# keyboard.net
KiCad netlist of a schematic drawn in EAGLE
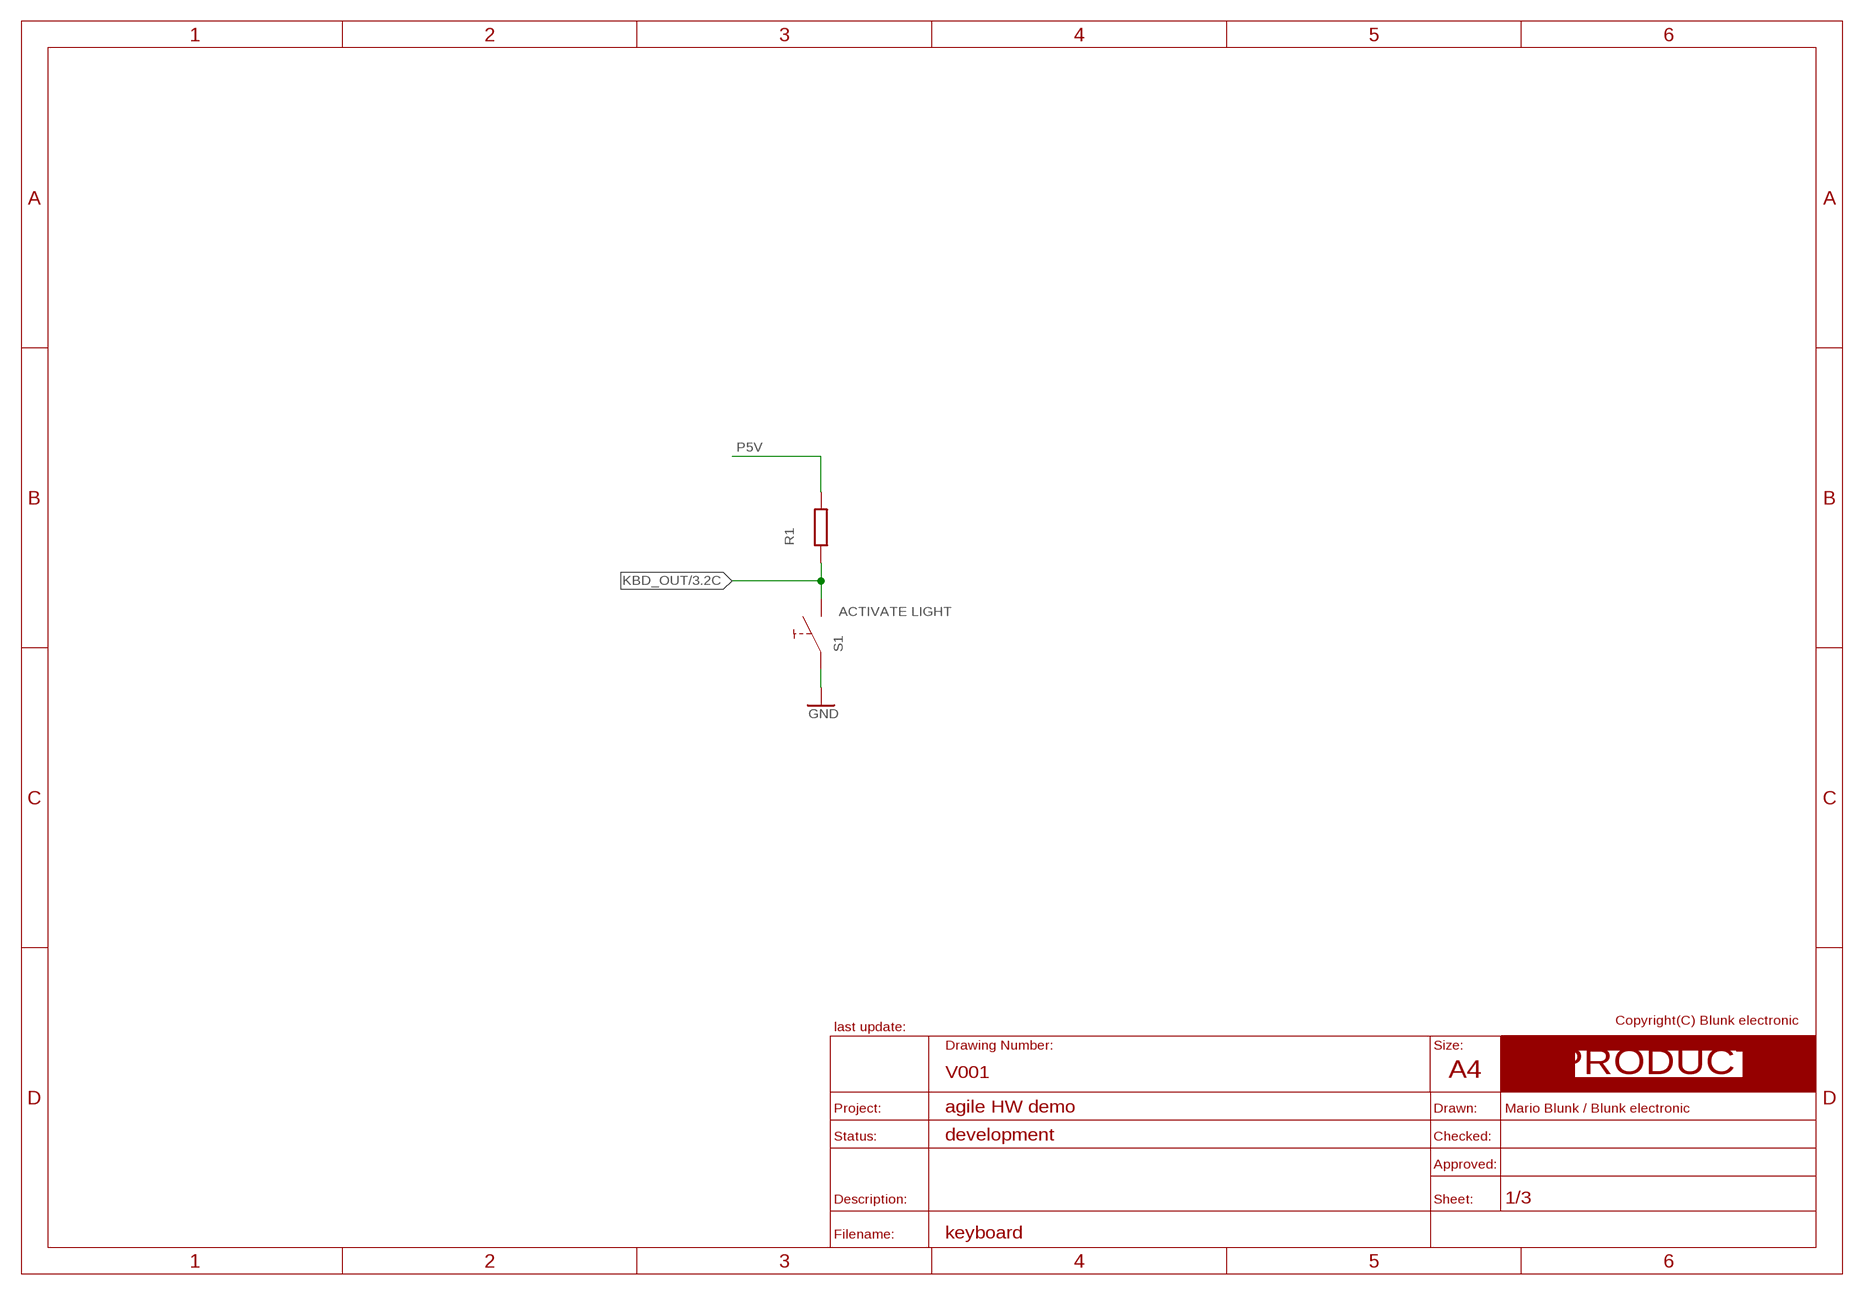
[diagram p0: schematic, sheet 1]
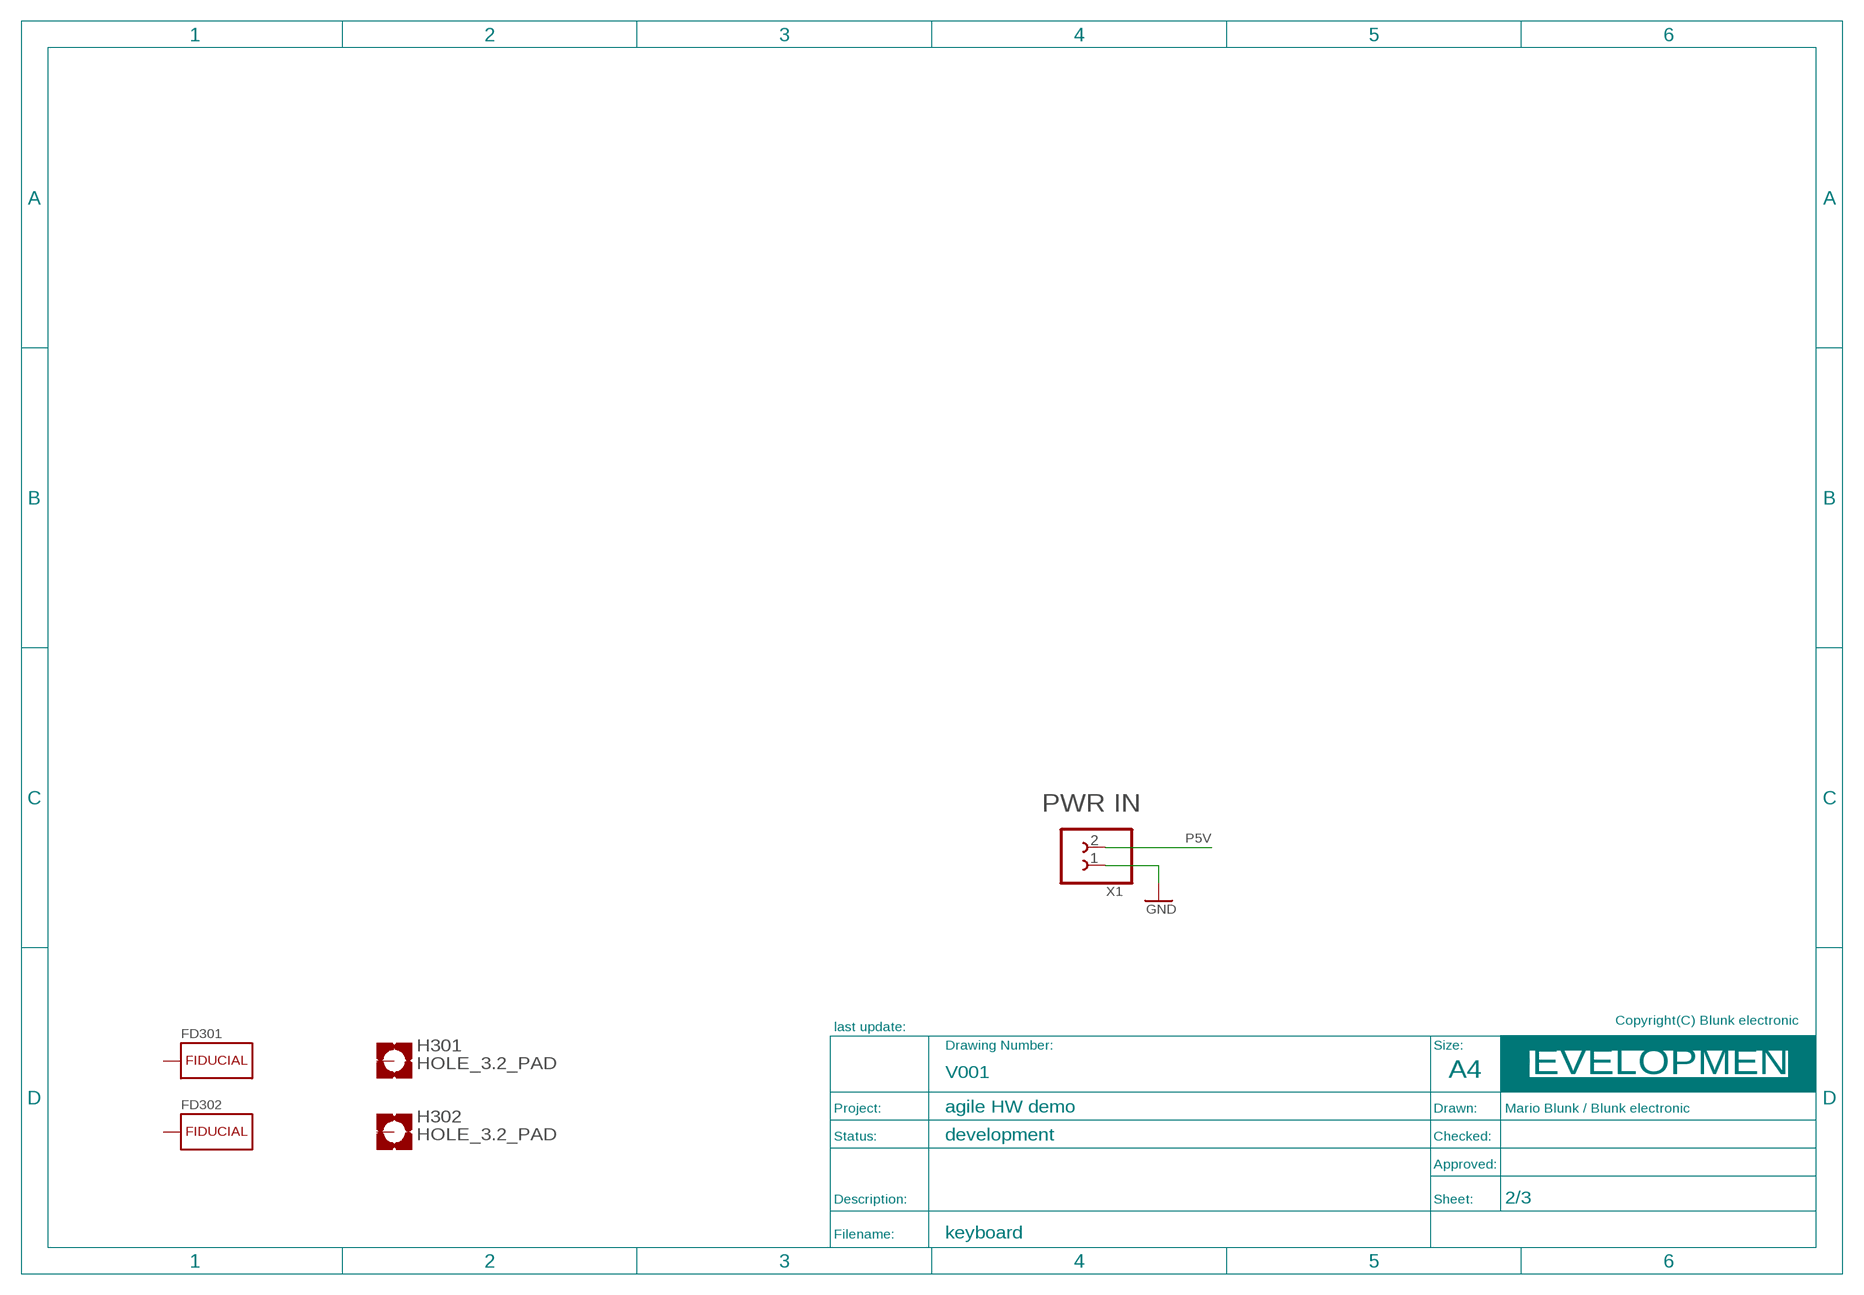
[diagram p1: schematic, sheet 2]
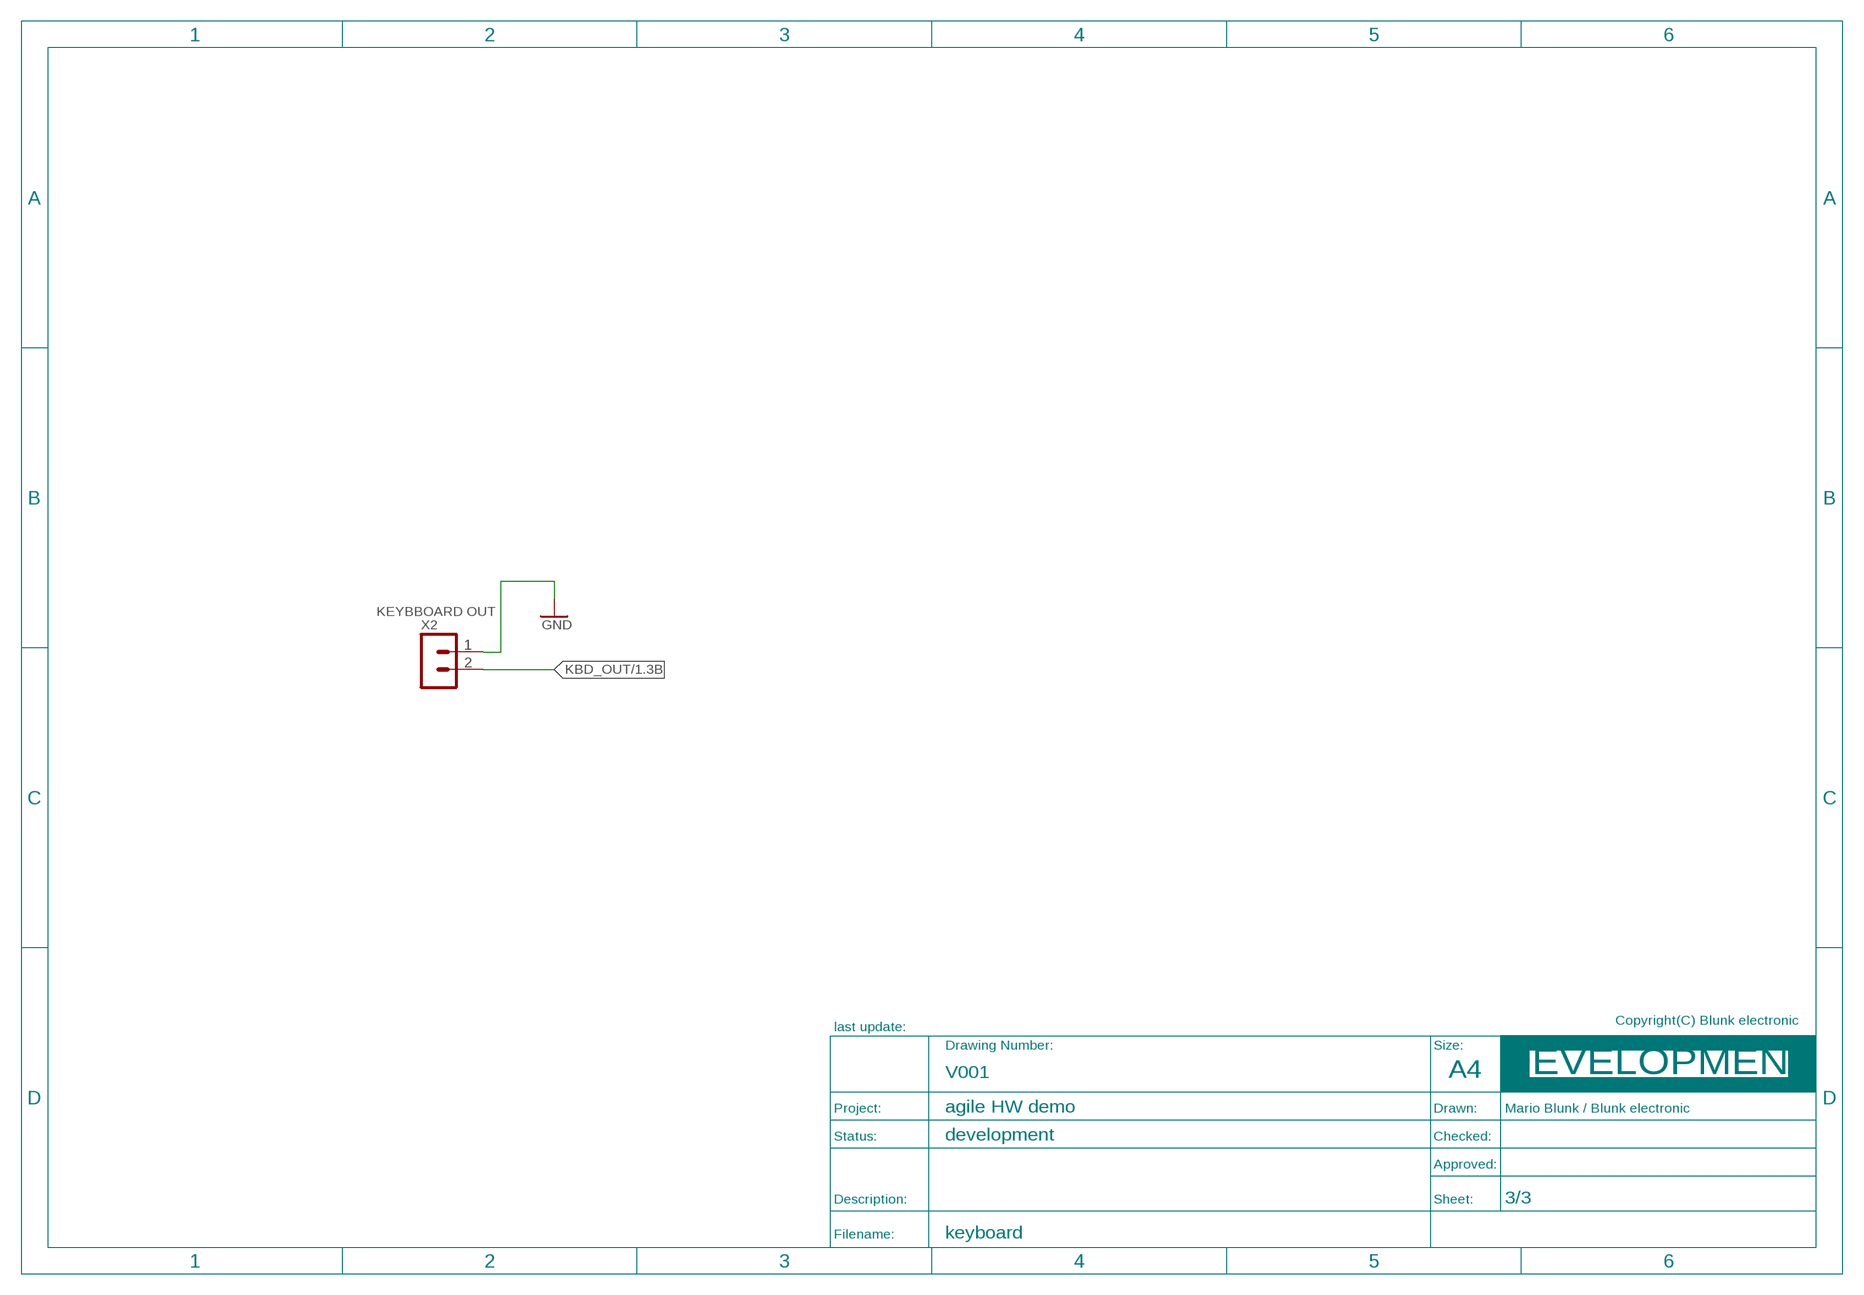
[diagram p2: schematic, sheet 3]

(export (version "E")
  (design (tool "Eeschema 10.0.6"))
  (components
    (comp (ref "FD301")
      (value "FIDUCIAL_CROSSHAIR")
      (footprint "eagle-import:CROSSHAIR")
      (libsource (lib "eagle-import") (part "FIDUCIAL_CROSSHAIR"))
    )
    (comp (ref "FD302")
      (value "FIDUCIAL_CROSSHAIR")
      (footprint "eagle-import:CROSSHAIR")
      (libsource (lib "eagle-import") (part "FIDUCIAL_CROSSHAIR"))
    )
    (comp (ref "H301")
      (value "HOLE_3.2_PAD")
      (footprint "eagle-import:3.2_PAD")
      (libsource (lib "eagle-import") (part "HOLE_3.2_PAD"))
    )
    (comp (ref "H302")
      (value "HOLE_3.2_PAD")
      (footprint "eagle-import:3.2_PAD")
      (libsource (lib "eagle-import") (part "HOLE_3.2_PAD"))
    )
    (comp (ref "X1")
      (value "CLAMP_1X2-T-2.5MM")
      (footprint "eagle-import:T_WIRE_CLAMP_1X2_PITCH_2MM5")
      (fields (field (name "FUNCTION") "PWR IN"))
      (libsource (lib "eagle-import") (part "CLAMP_1X2-T-2.5MM"))
    )
    (comp (ref "R1")
      (value "R_S_0805")
      (footprint "eagle-import:S_0805")
      (libsource (lib "eagle-import") (part "R_S_0805"))
    )
    (comp (ref "S1")
      (value "PUSH_BUTTON_S_6X6MM")
      (footprint "eagle-import:S_PUSH_BUTTON_6X6")
      (fields (field (name "FUNCTION") "ACTIVATE LIGHT"))
      (libsource (lib "eagle-import") (part "PUSH_BUTTON_S_6X6MM"))
    )
    (comp (ref "X2")
      (value "MALE_2X1-T-VERTICAL")
      (footprint "eagle-import:T_MALE_2X1_VERTICAL_PITCH_2MM54")
      (fields (field (name "FUNCTION") "KEYBBOARD OUT"))
      (libsource (lib "eagle-import") (part "MALE_2X1-T-VERTICAL"))
    )
  )
  (nets
    (net (code "1") (name "GND") (class "Default")
      (node (ref "S1") (pin "A") (pinfunction "A1_A") (pintype "passive"))
      (node (ref "S1") (pin "A1") (pinfunction "A1_A1") (pintype "passive"))
      (node (ref "X1") (pin "1") (pinfunction "1_1") (pintype "passive"))
      (node (ref "X2") (pin "1") (pinfunction "1_1") (pintype "passive"))
    )
    (net (code "2") (name "KBD_OUT") (class "Default")
      (node (ref "R1") (pin "1") (pinfunction "1_1") (pintype "passive"))
      (node (ref "S1") (pin "B") (pinfunction "B1_B") (pintype "passive"))
      (node (ref "S1") (pin "B1") (pinfunction "B1_B1") (pintype "passive"))
      (node (ref "X2") (pin "2") (pinfunction "2_2") (pintype "passive"))
    )
    (net (code "3") (name "P5V") (class "Default")
      (node (ref "R1") (pin "2") (pinfunction "2_2") (pintype "passive"))
      (node (ref "X1") (pin "2") (pinfunction "2_2") (pintype "passive"))
    )
    (net (code "4") (name "unconnected-(FD301-NC-Pad1)") (class "Default")
      (node (ref "FD301") (pin "1") (pinfunction "NC_1") (pintype "no_connect"))
    )
    (net (code "5") (name "unconnected-(FD302-NC-Pad1)") (class "Default")
      (node (ref "FD302") (pin "1") (pinfunction "NC_1") (pintype "no_connect"))
    )
    (net (code "6") (name "unconnected-(H301-MOUNT-PadH1)") (class "Default")
      (node (ref "H301") (pin "H1") (pinfunction "MOUNT_H1") (pintype "passive"))
    )
    (net (code "7") (name "unconnected-(H302-MOUNT-PadH1)") (class "Default")
      (node (ref "H302") (pin "H1") (pinfunction "MOUNT_H1") (pintype "passive"))
    )
  )
)
